# PMIC.net
KiCad netlist of a schematic drawn in Altium Designer
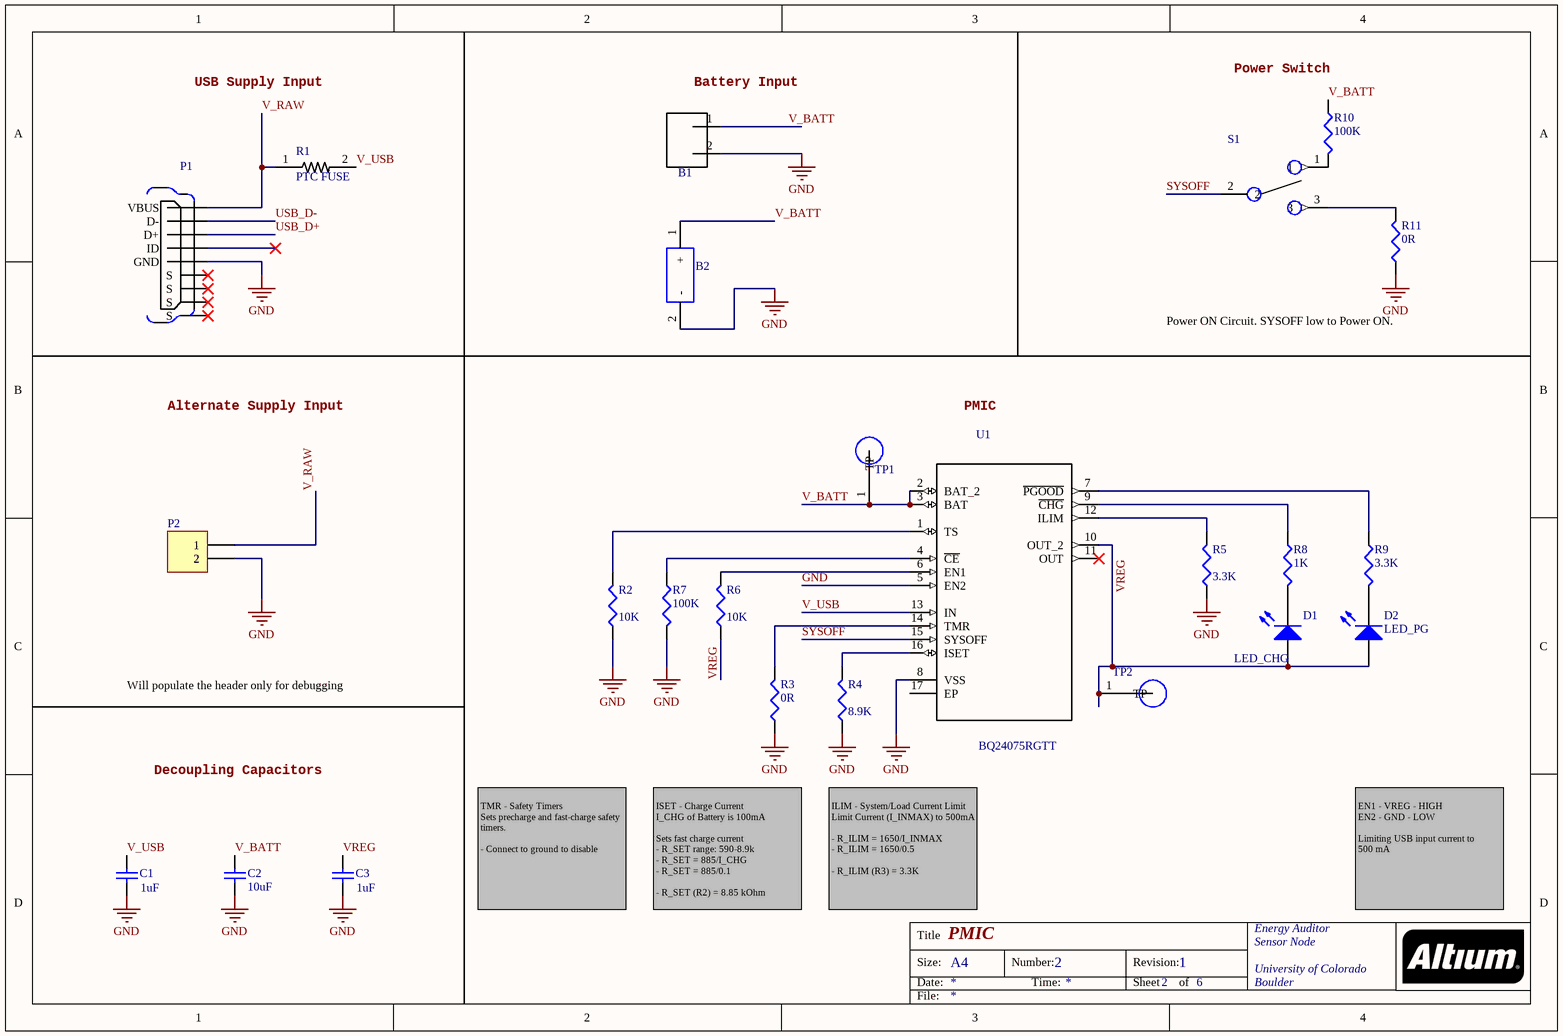
[diagram p0: PMIC.SchDoc]

(export (version "E")
  (design (tool "Eeschema 10.0.6"))
  (components
    (comp (ref "B1")
      (value "S2B-PH-SM4-TB(LF)(SN)")
      (footprint "S2B-PH-SM4-TB(LF)(SN)")
      (description "PH Series 2 Position 2 mm Pitch Surface Mount Side Entry Shrouded Header")
      (fields
        (field (name "MANUFACTURER") "JST Sales America Inc.")
        (field (name "DIGI-KEY PART NUMBER") "455-1749-1-ND")
      )
      (libsource (lib "S2B-PH-SM4-TB_LF__SN_") (part "S2B-PH-SM4-TB(LF)(SN)"))
    )
    (comp (ref "B2")
      (value "SMTU2450N-LF_BULK")
      (footprint "SMTU2430-LF")
      (description "Coin Cell Battery Holders SFC MNT FOR CR2450N")
      (fields (field (name "MOUSER PART NUMBER") "614-SMTU2450N-LF") (field (name "MANUFACTURER") "RENATA"))
      (libsource (lib "SMTU2450N-LF_BULK") (part "SMTU2450N-LF_BULK"))
    )
    (comp (ref "C1")
      (value "1uF")
      (footprint "1608[0603]")
      (description "CAP CER 1UF 16V X7R 0603")
      (fields
        (field (name "DIGI-KEY PART NUMBER") "1276-6524-1-ND")
        (field (name "MANUFACTURER") "Samsung Electro-Mechanics")
      )
      (libsource (lib "Miscellaneous Devices") (part "Cap"))
    )
    (comp (ref "C2")
      (value "10uF")
      (footprint "1608[0603]")
      (description "CAP CER 10UF 10V X5R 0603")
      (fields
        (field (name "DIGI-KEY PART NUMBER") "490-10474-1-ND")
        (field (name "MANUFACTURER") "Murata Electronics North America")
      )
      (libsource (lib "Miscellaneous Devices") (part "Cap Semi"))
    )
    (comp (ref "C3")
      (value "1uF")
      (footprint "1608[0603]")
      (description "CAP CER 1UF 16V X7R 0603")
      (fields
        (field (name "DIGI-KEY PART NUMBER") "1276-6524-1-ND")
        (field (name "MANUFACTURER") "Samsung Electro-Mechanics")
      )
      (libsource (lib "Miscellaneous Devices") (part "Cap"))
    )
    (comp (ref "D1")
      (value "LED_CHG")
      (footprint "1608[0603]")
      (description "Blue 470nm LED Indication - Discrete 2.85V 0603 (1608 Metric)")
      (fields
        (field (name "DIGI-KEY PART NUMBER") "475-2816-1-ND")
        (field (name "MANUFACTURER") "OSRAM Opto Semiconductors Inc.")
      )
      (libsource (lib "Miscellaneous Devices") (part "LED2"))
    )
    (comp (ref "D2")
      (value "LED_PG")
      (footprint "1608[0603]")
      (description "LED GREEN DIFFUSED 0603 SMD")
      (fields
        (field (name "DIGI-KEY PART NUMBER") "475-3118-1-ND")
        (field (name "MANUFACTURER") "OSRAM Opto Semiconductors Inc.")
      )
      (libsource (lib "Miscellaneous Devices") (part "LED2"))
    )
    (comp (ref "P1")
      (value "10104111-0001LF")
      (footprint "FRAMATOME_10104111-0001LF")
      (description "Micro Usb, 2.0 Type Ab, Receptacle, Th")
      (fields
        (field (name "DIGI-KEY PART NUMBER") "609-4053-1-ND")
        (field (name "MANUFACTURER") "Amphenol FCI")
      )
      (libsource (lib "USB-connector") (part "10104111-0001LF"))
    )
    (comp (ref "P2")
      (value "Header 2")
      (footprint "HDR1X2")
      (description "Header, 2-Pin")
      (libsource (lib "Miscellaneous Connectors") (part "Header 2"))
    )
    (comp (ref "R1")
      (value "PTC FUSE")
      (footprint "RESC3216X125N")
      (description "PTC RESET FUSE 6V 500MA 1206")
      (fields
        (field (name "MANUFACTURER") "Bel Fuse")
        (field (name "MANUFACTURER PART NUMBER") "Littelfuse Inc.")
      )
      (libsource (lib "PTC-1206") (part "0ZCA0075FF2G"))
    )
    (comp (ref "R2")
      (value "10K")
      (footprint "1608[0603]")
      (description "RES SMD 10K OHM 1% 1/8W 0603")
      (fields
        (field (name "DIGI-KEY PART NUMBER") "MCT0603-10.0K-CFCT-ND")
        (field (name "MANUFACTURER") "Vishay Beyschlag")
      )
      (libsource (lib "Miscellaneous Devices") (part "Res3"))
    )
    (comp (ref "R3")
      (value "0R")
      (footprint "1608[0603]")
      (description "RES 0 OHM JUMPER 1/8W 0603")
      (fields
        (field (name "DIGI-KEY PART NUMBER") "749-1745-1-ND")
        (field (name "MANUFACTURER") "Vishay Beyschlag")
      )
      (libsource (lib "Miscellaneous Devices") (part "Res3"))
    )
    (comp (ref "R4")
      (value "8.9K")
      (footprint "1608[0603]")
      (description "RES SMD 8.87KOHM 0.5% 1/10W 0603")
      (fields (field (name "DIGI-KEY PART NUMBER") "311-8.87KDCT-ND") (field (name "MANUFACTURER") "Yageo"))
      (libsource (lib "Miscellaneous Devices") (part "Res3"))
    )
    (comp (ref "R5")
      (value "3.3K")
      (footprint "1608[0603]")
      (description "RES SMD 3.3K OHM 5% 1/10W 0603")
      (fields
        (field (name "DIGI-KEY PART NUMBER") "P3.3KGCT-ND")
        (field (name "MANUFACTURER") "Panasonic Electronic Components")
      )
      (libsource (lib "Miscellaneous Devices") (part "Res3"))
    )
    (comp (ref "R6")
      (value "10K")
      (footprint "1608[0603]")
      (description "RES SMD 10K OHM 1% 1/8W 0603")
      (fields
        (field (name "DIGI-KEY PART NUMBER") "MCT0603-10.0K-CFCT-ND")
        (field (name "MANUFACTURER") "Vishay Beyschlag")
      )
      (libsource (lib "Miscellaneous Devices") (part "Res3"))
    )
    (comp (ref "R7")
      (value "100K")
      (footprint "1608[0603]")
      (description "RES SMD 100K OHM 0.1% 1/10W 0603")
      (fields
        (field (name "MANUFACTURER") "Susumu")
        (field (name "MANUFACTURER PART NUMBER") "RG1608P-104-B-T5")
      )
      (libsource (lib "Miscellaneous Devices") (part "Res3"))
    )
    (comp (ref "R8")
      (value "1K")
      (footprint "1608[0603]")
      (description "RES SMD 1K OHM 0.1% 1/10W 0603")
      (fields (field (name "DIGI-KEY PART NUMBER") "YAG1237CT-ND") (field (name "MANUFACTURER") "Yageo"))
      (libsource (lib "Miscellaneous Devices") (part "Res3"))
    )
    (comp (ref "R9")
      (value "3.3K")
      (footprint "1608[0603]")
      (description "RES SMD 3.3K OHM 5% 1/10W 0603")
      (fields
        (field (name "DIGI-KEY PART NUMBER") "P3.3KGCT-ND")
        (field (name "MANUFACTURER") "Panasonic Electronic Components")
      )
      (libsource (lib "Miscellaneous Devices") (part "Res3"))
    )
    (comp (ref "R10")
      (value "100K")
      (footprint "1608[0603]")
      (description "RES SMD 100K OHM 0.1% 1/10W 0603")
      (fields
        (field (name "MANUFACTURER") "Susumu")
        (field (name "MANUFACTURER PART NUMBER") "RG1608P-104-B-T5")
      )
      (libsource (lib "Miscellaneous Devices") (part "Res3"))
    )
    (comp (ref "R11")
      (value "0R")
      (footprint "1608[0603]")
      (description "RES 0 OHM JUMPER 1/8W 0603")
      (fields
        (field (name "DIGI-KEY PART NUMBER") "749-1745-1-ND")
        (field (name "MANUFACTURER") "Vishay Beyschlag")
      )
      (libsource (lib "Miscellaneous Devices") (part "Res3"))
    )
    (comp (ref "S1")
      (value "AYZ0102AGRLC")
      (footprint "SW_AYZ0102AGRLC")
      (description "SWITCH SLIDE SPDT 100MA 12V")
      (fields (field (name "DIGI-KEY PART NUMBER") "401-2012-1-ND") (field (name "MANUFACTURER") "C&K"))
      (libsource (lib "AYZ0102AGRLC") (part "AYZ0102AGRLC"))
    )
    (comp (ref "TP1")
      (value "5019")
      (footprint "TP380X203")
      (description "Phosphor Bronze Contact Miniature Silver Plated Surface Mount Test Points")
      (fields (field (name "DIGI-KEY PART NUMBER") "36-5019CT-ND") (field (name "MANUFACTURER") "Keystone"))
      (libsource (lib "5019") (part "5019"))
    )
    (comp (ref "TP2")
      (value "5019")
      (footprint "TP380X203")
      (description "Phosphor Bronze Contact Miniature Silver Plated Surface Mount Test Points")
      (fields (field (name "DIGI-KEY PART NUMBER") "36-5019CT-ND") (field (name "MANUFACTURER") "Keystone"))
      (libsource (lib "5019") (part "5019"))
    )
    (comp (ref "U1")
      (value "BQ24075RGTT")
      (footprint "QFN50P300X300X100-17N")
      (description "USB-Friendly Li-Ion Battery Charger and Power-Path Management IC, Vout 5.5V 16-QFN -40 to 85")
      (fields
        (field (name "MANUFACTURER") "Texas Instruments")
        (field (name "DIGI-KEY PART NUMBER") "296-38874-1-ND")
      )
      (libsource (lib "BQ24075RGTT") (part "BQ24075RGTT"))
    )
  )
  (nets
    (net (code "1") (name "/SYSOFF") (class "Default")
      (node (ref "S1") (pin "2") (pinfunction "2_2") (pintype "power_in"))
      (node (ref "U1") (pin "15") (pinfunction "SYSOFF_15") (pintype "input"))
    )
    (net (code "2") (name "/USB_D+") (class "Default")
      (node (ref "P1") (pin "3") (pinfunction "D+_3") (pintype "passive"))
    )
    (net (code "3") (name "/USB_D-") (class "Default")
      (node (ref "P1") (pin "2") (pinfunction "D-_2") (pintype "passive"))
    )
    (net (code "4") (name "/VREG") (class "Default")
      (node (ref "C3") (pin "2") (pinfunction "2_2") (pintype "passive"))
      (node (ref "D1") (pin "1") (pinfunction "A_1") (pintype "passive"))
      (node (ref "D2") (pin "1") (pinfunction "A_1") (pintype "passive"))
      (node (ref "R6") (pin "1") (pinfunction "1_1") (pintype "passive"))
      (node (ref "TP2") (pin "1") (pinfunction "TP_1") (pintype "passive"))
      (node (ref "U1") (pin "10") (pinfunction "OUT_2_10") (pintype "output"))
    )
    (net (code "5") (name "/V_BATT") (class "Default")
      (node (ref "B1") (pin "1") (pinfunction "1_1") (pintype "passive"))
      (node (ref "B2") (pin "1") (pinfunction "+_1") (pintype "passive"))
      (node (ref "C2") (pin "2") (pinfunction "2_2") (pintype "passive"))
      (node (ref "R10") (pin "1") (pinfunction "1_1") (pintype "passive"))
      (node (ref "TP1") (pin "1") (pinfunction "TP_1") (pintype "passive"))
      (node (ref "U1") (pin "2") (pinfunction "BAT_2_2") (pintype "bidirectional"))
      (node (ref "U1") (pin "3") (pinfunction "BAT_3") (pintype "bidirectional"))
    )
    (net (code "6") (name "/V_RAW") (class "Default")
      (node (ref "P1") (pin "1") (pinfunction "VBUS_1") (pintype "power_in"))
      (node (ref "P2") (pin "1") (pinfunction "1_1") (pintype "passive"))
      (node (ref "R1") (pin "1") (pinfunction "1_1") (pintype "passive"))
    )
    (net (code "7") (name "/V_USB") (class "Default")
      (node (ref "C1") (pin "2") (pinfunction "2_2") (pintype "passive"))
      (node (ref "R1") (pin "2") (pinfunction "2_2") (pintype "passive"))
      (node (ref "U1") (pin "13") (pinfunction "IN_13") (pintype "input"))
    )
    (net (code "8") (name "GND") (class "Default")
      (node (ref "B1") (pin "2") (pinfunction "2_2") (pintype "passive"))
      (node (ref "B2") (pin "2") (pinfunction "-_2") (pintype "passive"))
      (node (ref "C1") (pin "1") (pinfunction "1_1") (pintype "passive"))
      (node (ref "C2") (pin "1") (pinfunction "1_1") (pintype "passive"))
      (node (ref "C3") (pin "1") (pinfunction "1_1") (pintype "passive"))
      (node (ref "P1") (pin "5") (pinfunction "GND_5") (pintype "power_in"))
      (node (ref "P2") (pin "2") (pinfunction "2_2") (pintype "passive"))
      (node (ref "R11") (pin "1") (pinfunction "1_1") (pintype "passive"))
      (node (ref "R2") (pin "1") (pinfunction "1_1") (pintype "passive"))
      (node (ref "R3") (pin "1") (pinfunction "1_1") (pintype "passive"))
      (node (ref "R4") (pin "1") (pinfunction "1_1") (pintype "passive"))
      (node (ref "R5") (pin "1") (pinfunction "1_1") (pintype "passive"))
      (node (ref "R7") (pin "2") (pinfunction "2_2") (pintype "passive"))
      (node (ref "U1") (pin "5") (pinfunction "EN2_5") (pintype "input"))
      (node (ref "U1") (pin "8") (pinfunction "VSS_8") (pintype "passive"))
    )
    (net (code "9") (name "Net-(D1-K)") (class "Default")
      (node (ref "D1") (pin "2") (pinfunction "K_2") (pintype "passive"))
      (node (ref "R8") (pin "2") (pinfunction "2_2") (pintype "passive"))
    )
    (net (code "10") (name "Net-(D2-K)") (class "Default")
      (node (ref "D2") (pin "2") (pinfunction "K_2") (pintype "passive"))
      (node (ref "R9") (pin "2") (pinfunction "2_2") (pintype "passive"))
    )
    (net (code "11") (name "Net-(R10-Pad2)") (class "Default")
      (node (ref "R10") (pin "2") (pinfunction "2_2") (pintype "passive"))
      (node (ref "S1") (pin "1") (pinfunction "1_1") (pintype "output"))
    )
    (net (code "12") (name "Net-(R11-Pad2)") (class "Default")
      (node (ref "R11") (pin "2") (pinfunction "2_2") (pintype "passive"))
      (node (ref "S1") (pin "3") (pinfunction "3_3") (pintype "output"))
    )
    (net (code "13") (name "Net-(U1-EN1)") (class "Default")
      (node (ref "R6") (pin "2") (pinfunction "2_2") (pintype "passive"))
      (node (ref "U1") (pin "6") (pinfunction "EN1_6") (pintype "input"))
    )
    (net (code "14") (name "Net-(U1-ILIM)") (class "Default")
      (node (ref "R5") (pin "2") (pinfunction "2_2") (pintype "passive"))
      (node (ref "U1") (pin "12") (pinfunction "ILIM_12") (pintype "output"))
    )
    (net (code "15") (name "Net-(U1-ISET)") (class "Default")
      (node (ref "R4") (pin "2") (pinfunction "2_2") (pintype "passive"))
      (node (ref "U1") (pin "16") (pinfunction "ISET_16") (pintype "bidirectional"))
    )
    (net (code "16") (name "Net-(U1-TMR)") (class "Default")
      (node (ref "R3") (pin "2") (pinfunction "2_2") (pintype "passive"))
      (node (ref "U1") (pin "14") (pinfunction "TMR_14") (pintype "input"))
    )
    (net (code "17") (name "Net-(U1-TS)") (class "Default")
      (node (ref "R2") (pin "2") (pinfunction "2_2") (pintype "passive"))
      (node (ref "U1") (pin "1") (pinfunction "TS_1") (pintype "bidirectional"))
    )
    (net (code "18") (name "Net-(U1-~{CE})") (class "Default")
      (node (ref "R7") (pin "1") (pinfunction "1_1") (pintype "passive"))
      (node (ref "U1") (pin "4") (pinfunction "~{CE}_4") (pintype "input"))
    )
    (net (code "19") (name "Net-(U1-~{CHG})") (class "Default")
      (node (ref "R8") (pin "1") (pinfunction "1_1") (pintype "passive"))
      (node (ref "U1") (pin "9") (pinfunction "~{CHG}_9") (pintype "output"))
    )
    (net (code "20") (name "Net-(U1-~{PGOOD})") (class "Default")
      (node (ref "R9") (pin "1") (pinfunction "1_1") (pintype "passive"))
      (node (ref "U1") (pin "7") (pinfunction "~{PGOOD}_7") (pintype "output"))
    )
    (net (code "21") (name "unconnected-(P1-ID-Pad4)") (class "Default")
      (node (ref "P1") (pin "4") (pinfunction "ID_4") (pintype "passive+no_connect"))
    )
    (net (code "22") (name "unconnected-(P1-S-Pad6)") (class "Default")
      (node (ref "P1") (pin "6") (pinfunction "S_6") (pintype "power_in+no_connect"))
    )
    (net (code "23") (name "unconnected-(P1-S-Pad7)") (class "Default")
      (node (ref "P1") (pin "7") (pinfunction "S_7") (pintype "power_in+no_connect"))
    )
    (net (code "24") (name "unconnected-(P1-S-Pad8)") (class "Default")
      (node (ref "P1") (pin "8") (pinfunction "S_8") (pintype "power_in+no_connect"))
    )
    (net (code "25") (name "unconnected-(P1-S-Pad9)") (class "Default")
      (node (ref "P1") (pin "9") (pinfunction "S_9") (pintype "power_in+no_connect"))
    )
    (net (code "26") (name "unconnected-(U1-EP-Pad17)") (class "Default")
      (node (ref "U1") (pin "17") (pinfunction "EP_17") (pintype "passive"))
    )
    (net (code "27") (name "unconnected-(U1-OUT-Pad11)") (class "Default")
      (node (ref "U1") (pin "11") (pinfunction "OUT_11") (pintype "output+no_connect"))
    )
  )
)
